# DSN.net
KiCad netlist of a schematic drawn in Altium Designer
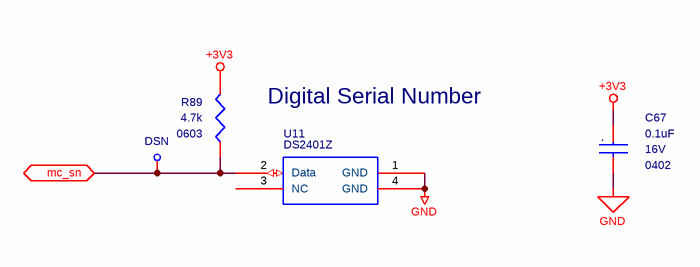
[diagram p0: DSN.SchDoc]

(export (version "E")
  (design (tool "Eeschema 10.0.6"))
  (components
    (comp (ref "C67")
      (value "0.1uF")
      (footprint "MC_S6/SM/C_0402_IPC")
      (description "CAP CER 0.1UF 16V X7R 0402")
      (fields
        (field (name "MANUFACTURER") "KEMET")
        (field (name "MANUFACTURER PART NUMBER") "C0402C104K4RACTU")
        (field (name "PACKAGE") "0402")
        (field (name "VOLTAGE - RATED") "16V")
      )
      (libsource (lib "ALCT_MEZ_SPARTAN6_Library") (part "C0402C104K4RACTU"))
    )
    (comp (ref "DSN")
      (value "Test Point Via")
      (footprint "MC_S6/TH/TPVIA")
      (libsource (lib "ALCT_MEZ_SPARTAN6_Library") (part "TPVIA"))
    )
    (comp (ref "R89")
      (value "4.7k")
      (footprint "MC_S6/SM/R_0603_IPC")
      (description "RES SMD 4.7K OHM 1% 1/10W 0603")
      (fields
        (field (name "MANUFACTURER") "Bourns Inc.")
        (field (name "MANUFACTURER PART NUMBER") "CR0603-FX-4701ELF")
        (field (name "SUPPLIER DEVICE PACKAGE") "0603")
      )
      (libsource (lib "ALCT_MEZ_SPARTAN6_Library") (part "CR0603-FX-4701ELF"))
    )
    (comp (ref "U11")
      (value "DS2401Z")
      (footprint "MC_S6/SM/SOT223_1243")
      (description "IC Digital Serial Number")
      (fields
        (field (name "MANUFACTURER") "Maxim Integrated")
        (field (name "MANUFACTURER PART NUMBER") "DS2401Z+T&R")
      )
      (libsource (lib "ALCT_MEZ_SPARTAN6_Library") (part "DS2401_sot223"))
    )
  )
  (nets
    (net (code "1") (name "+3V3") (class "Default")
      (node (ref "C67") (pin "1") (pinfunction "1_1") (pintype "passive"))
      (node (ref "R89") (pin "1") (pinfunction "1_1") (pintype "passive"))
    )
    (net (code "2") (name "/mc_sn") (class "Default")
      (node (ref "DSN") (pin "1") (pinfunction "In_1") (pintype "passive"))
      (node (ref "R89") (pin "2") (pinfunction "2_2") (pintype "passive"))
      (node (ref "U11") (pin "2") (pinfunction "Data_2") (pintype "bidirectional"))
    )
    (net (code "3") (name "GND") (class "Default")
      (node (ref "C67") (pin "2") (pinfunction "2_2") (pintype "passive"))
      (node (ref "U11") (pin "1") (pinfunction "GND_1") (pintype "power_in"))
      (node (ref "U11") (pin "4") (pinfunction "GND_4") (pintype "power_in"))
    )
    (net (code "4") (name "unconnected-(U11-NC-Pad3)") (class "Default")
      (node (ref "U11") (pin "3") (pinfunction "NC_3") (pintype "power_in"))
    )
  )
)
